# Main.net
KiCad netlist of a schematic drawn in Altium Designer
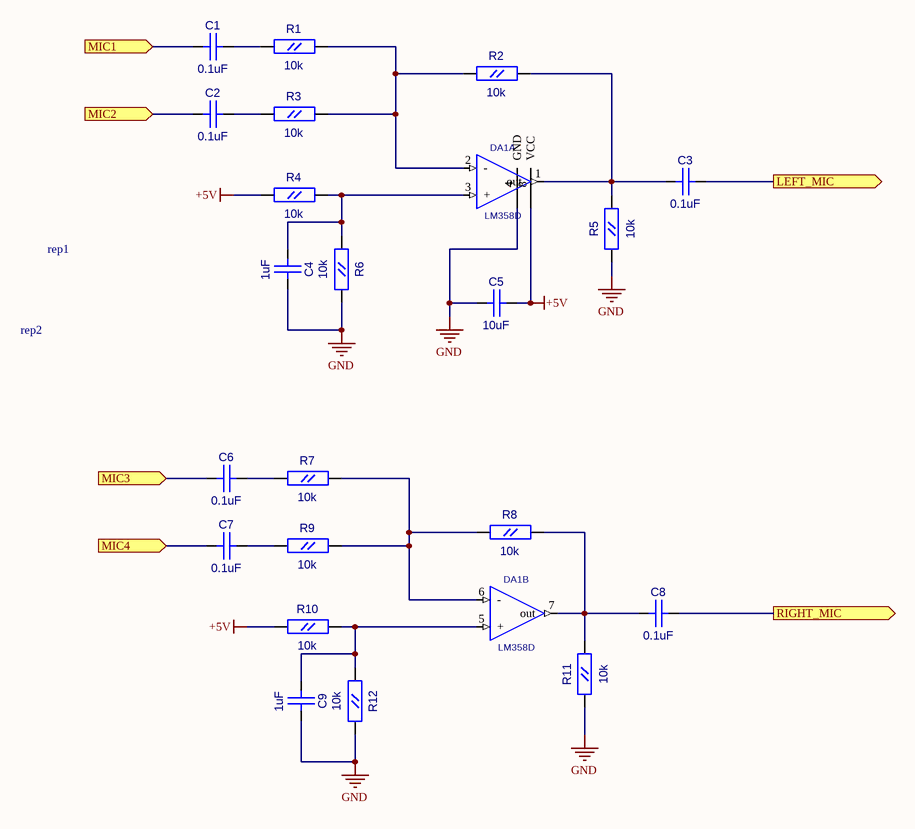
[diagram p0: Main.SchDoc]

(export (version "E")
  (design (tool "Eeschema 10.0.6"))
  (components
    (comp (ref "C1")
      (value "0.1uF")
      (footprint "CC0603")
      (description "CC0603")
      (libsource (lib "gprs_modem_2") (part "CC0603"))
    )
    (comp (ref "C2")
      (value "0.1uF")
      (footprint "CC0603")
      (description "CC0603")
      (libsource (lib "gprs_modem_2") (part "CC0603"))
    )
    (comp (ref "C3")
      (value "0.1uF")
      (footprint "CC0603")
      (description "CC0603")
      (libsource (lib "gprs_modem_2") (part "CC0603"))
    )
    (comp (ref "C4")
      (value "1uF")
      (footprint "CC0603")
      (description "CC0603")
      (libsource (lib "gprs_modem_2") (part "CC0603"))
    )
    (comp (ref "C5")
      (value "10uF")
      (footprint "CC0805")
      (description "CC0805")
      (libsource (lib "gprs_modem_2") (part "CC0805"))
    )
    (comp (ref "C6")
      (value "0.1uF")
      (footprint "CC0603")
      (description "CC0603")
      (libsource (lib "gprs_modem_2") (part "CC0603"))
    )
    (comp (ref "C7")
      (value "0.1uF")
      (footprint "CC0603")
      (description "CC0603")
      (libsource (lib "gprs_modem_2") (part "CC0603"))
    )
    (comp (ref "C8")
      (value "0.1uF")
      (footprint "CC0603")
      (description "CC0603")
      (libsource (lib "gprs_modem_2") (part "CC0603"))
    )
    (comp (ref "C9")
      (value "1uF")
      (footprint "CC0603")
      (description "CC0603")
      (libsource (lib "gprs_modem_2") (part "CC0603"))
    )
    (comp (ref "DA1") (value "LM358D") (footprint "SO-8") (libsource (lib "Schetchik") (part "LM358D")))
    (comp (ref "R1")
      (value "10k")
      (footprint "RC0603")
      (description "RC0603")
      (libsource (lib "gprs_modem_2") (part "RC0603"))
    )
    (comp (ref "R2")
      (value "10k")
      (footprint "RC0603")
      (description "RC0603")
      (libsource (lib "gprs_modem_2") (part "RC0603"))
    )
    (comp (ref "R3")
      (value "10k")
      (footprint "RC0603")
      (description "RC0603")
      (libsource (lib "gprs_modem_2") (part "RC0603"))
    )
    (comp (ref "R4")
      (value "10k")
      (footprint "RC0603")
      (description "RC0603")
      (libsource (lib "gprs_modem_2") (part "RC0603"))
    )
    (comp (ref "R5")
      (value "10k")
      (footprint "RC0603")
      (description "RC0603")
      (libsource (lib "gprs_modem_2") (part "RC0603"))
    )
    (comp (ref "R6")
      (value "10k")
      (footprint "RC0603")
      (description "RC0603")
      (libsource (lib "gprs_modem_2") (part "RC0603"))
    )
    (comp (ref "R7")
      (value "10k")
      (footprint "RC0603")
      (description "RC0603")
      (libsource (lib "gprs_modem_2") (part "RC0603"))
    )
    (comp (ref "R8")
      (value "10k")
      (footprint "RC0603")
      (description "RC0603")
      (libsource (lib "gprs_modem_2") (part "RC0603"))
    )
    (comp (ref "R9")
      (value "10k")
      (footprint "RC0603")
      (description "RC0603")
      (libsource (lib "gprs_modem_2") (part "RC0603"))
    )
    (comp (ref "R10")
      (value "10k")
      (footprint "RC0603")
      (description "RC0603")
      (libsource (lib "gprs_modem_2") (part "RC0603"))
    )
    (comp (ref "R11")
      (value "10k")
      (footprint "RC0603")
      (description "RC0603")
      (libsource (lib "gprs_modem_2") (part "RC0603"))
    )
    (comp (ref "R12")
      (value "10k")
      (footprint "RC0603")
      (description "RC0603")
      (libsource (lib "gprs_modem_2") (part "RC0603"))
    )
    (comp (ref "rep1")
      (value "REPER1.2")
      (footprint "REPER1.2")
      (libsource (lib "gprs_modem_2") (part "REPER1.2"))
    )
    (comp (ref "rep2")
      (value "REPER1.2")
      (footprint "REPER1.2")
      (libsource (lib "gprs_modem_2") (part "REPER1.2"))
    )
  )
  (nets
    (net (code "1") (name "+5V") (class "Default")
      (node (ref "C5") (pin "2") (pinfunction "B_2") (pintype "passive"))
      (node (ref "DA1") (pin "8") (pinfunction "VCC_8") (pintype "power_in"))
      (node (ref "R10") (pin "1") (pinfunction "A_1") (pintype "passive"))
      (node (ref "R4") (pin "1") (pinfunction "A_1") (pintype "passive"))
    )
    (net (code "2") (name "/LEFT_MIC") (class "Default")
      (node (ref "C3") (pin "2") (pinfunction "B_2") (pintype "passive"))
    )
    (net (code "3") (name "/MIC1") (class "Default")
      (node (ref "C1") (pin "1") (pinfunction "A_1") (pintype "passive"))
    )
    (net (code "4") (name "/MIC2") (class "Default")
      (node (ref "C2") (pin "1") (pinfunction "A_1") (pintype "passive"))
    )
    (net (code "5") (name "/MIC3") (class "Default")
      (node (ref "C6") (pin "1") (pinfunction "A_1") (pintype "passive"))
    )
    (net (code "6") (name "/MIC4") (class "Default")
      (node (ref "C7") (pin "1") (pinfunction "A_1") (pintype "passive"))
    )
    (net (code "7") (name "/RIGHT_MIC") (class "Default")
      (node (ref "C8") (pin "2") (pinfunction "B_2") (pintype "passive"))
    )
    (net (code "8") (name "GND") (class "Default")
      (node (ref "C4") (pin "2") (pinfunction "B_2") (pintype "passive"))
      (node (ref "C5") (pin "1") (pinfunction "A_1") (pintype "passive"))
      (node (ref "C9") (pin "2") (pinfunction "B_2") (pintype "passive"))
      (node (ref "DA1") (pin "4") (pinfunction "GND_4") (pintype "power_in"))
      (node (ref "R11") (pin "1") (pinfunction "A_1") (pintype "passive"))
      (node (ref "R12") (pin "2") (pinfunction "B_2") (pintype "passive"))
      (node (ref "R5") (pin "1") (pinfunction "A_1") (pintype "passive"))
      (node (ref "R6") (pin "2") (pinfunction "B_2") (pintype "passive"))
    )
    (net (code "9") (name "Net-(C1-B)") (class "Default")
      (node (ref "C1") (pin "2") (pinfunction "B_2") (pintype "passive"))
      (node (ref "R1") (pin "1") (pinfunction "A_1") (pintype "passive"))
    )
    (net (code "10") (name "Net-(C2-B)") (class "Default")
      (node (ref "C2") (pin "2") (pinfunction "B_2") (pintype "passive"))
      (node (ref "R3") (pin "1") (pinfunction "A_1") (pintype "passive"))
    )
    (net (code "11") (name "Net-(C3-A)") (class "Default")
      (node (ref "C3") (pin "1") (pinfunction "A_1") (pintype "passive"))
      (node (ref "DA1") (pin "1") (pinfunction "out_1") (pintype "output"))
      (node (ref "R2") (pin "2") (pinfunction "B_2") (pintype "passive"))
      (node (ref "R5") (pin "2") (pinfunction "B_2") (pintype "passive"))
    )
    (net (code "12") (name "Net-(C4-A)") (class "Default")
      (node (ref "C4") (pin "1") (pinfunction "A_1") (pintype "passive"))
      (node (ref "DA1") (pin "3") (pinfunction "+_3") (pintype "input"))
      (node (ref "R4") (pin "2") (pinfunction "B_2") (pintype "passive"))
      (node (ref "R6") (pin "1") (pinfunction "A_1") (pintype "passive"))
    )
    (net (code "13") (name "Net-(C6-B)") (class "Default")
      (node (ref "C6") (pin "2") (pinfunction "B_2") (pintype "passive"))
      (node (ref "R7") (pin "1") (pinfunction "A_1") (pintype "passive"))
    )
    (net (code "14") (name "Net-(C7-B)") (class "Default")
      (node (ref "C7") (pin "2") (pinfunction "B_2") (pintype "passive"))
      (node (ref "R9") (pin "1") (pinfunction "A_1") (pintype "passive"))
    )
    (net (code "15") (name "Net-(C8-A)") (class "Default")
      (node (ref "C8") (pin "1") (pinfunction "A_1") (pintype "passive"))
      (node (ref "DA1") (pin "7") (pinfunction "out_7") (pintype "output"))
      (node (ref "R11") (pin "2") (pinfunction "B_2") (pintype "passive"))
      (node (ref "R8") (pin "2") (pinfunction "B_2") (pintype "passive"))
    )
    (net (code "16") (name "Net-(C9-A)") (class "Default")
      (node (ref "C9") (pin "1") (pinfunction "A_1") (pintype "passive"))
      (node (ref "DA1") (pin "5") (pinfunction "+_5") (pintype "input"))
      (node (ref "R10") (pin "2") (pinfunction "B_2") (pintype "passive"))
      (node (ref "R12") (pin "1") (pinfunction "A_1") (pintype "passive"))
    )
    (net (code "17") (name "Net-(DA1A--)") (class "Default")
      (node (ref "DA1") (pin "2") (pinfunction "-_2") (pintype "input"))
      (node (ref "R1") (pin "2") (pinfunction "B_2") (pintype "passive"))
      (node (ref "R2") (pin "1") (pinfunction "A_1") (pintype "passive"))
      (node (ref "R3") (pin "2") (pinfunction "B_2") (pintype "passive"))
    )
    (net (code "18") (name "Net-(DA1B--)") (class "Default")
      (node (ref "DA1") (pin "6") (pinfunction "-_6") (pintype "input"))
      (node (ref "R7") (pin "2") (pinfunction "B_2") (pintype "passive"))
      (node (ref "R8") (pin "1") (pinfunction "A_1") (pintype "passive"))
      (node (ref "R9") (pin "2") (pinfunction "B_2") (pintype "passive"))
    )
    (net (code "19") (name "unconnected-(rep1-Pad1)") (class "Default")
      (node (ref "rep1") (pin "1") (pintype "passive"))
    )
    (net (code "20") (name "unconnected-(rep2-Pad1)") (class "Default")
      (node (ref "rep2") (pin "1") (pintype "passive"))
    )
  )
)
